# CPLD.net
KiCad netlist of a schematic drawn in Altium Designer
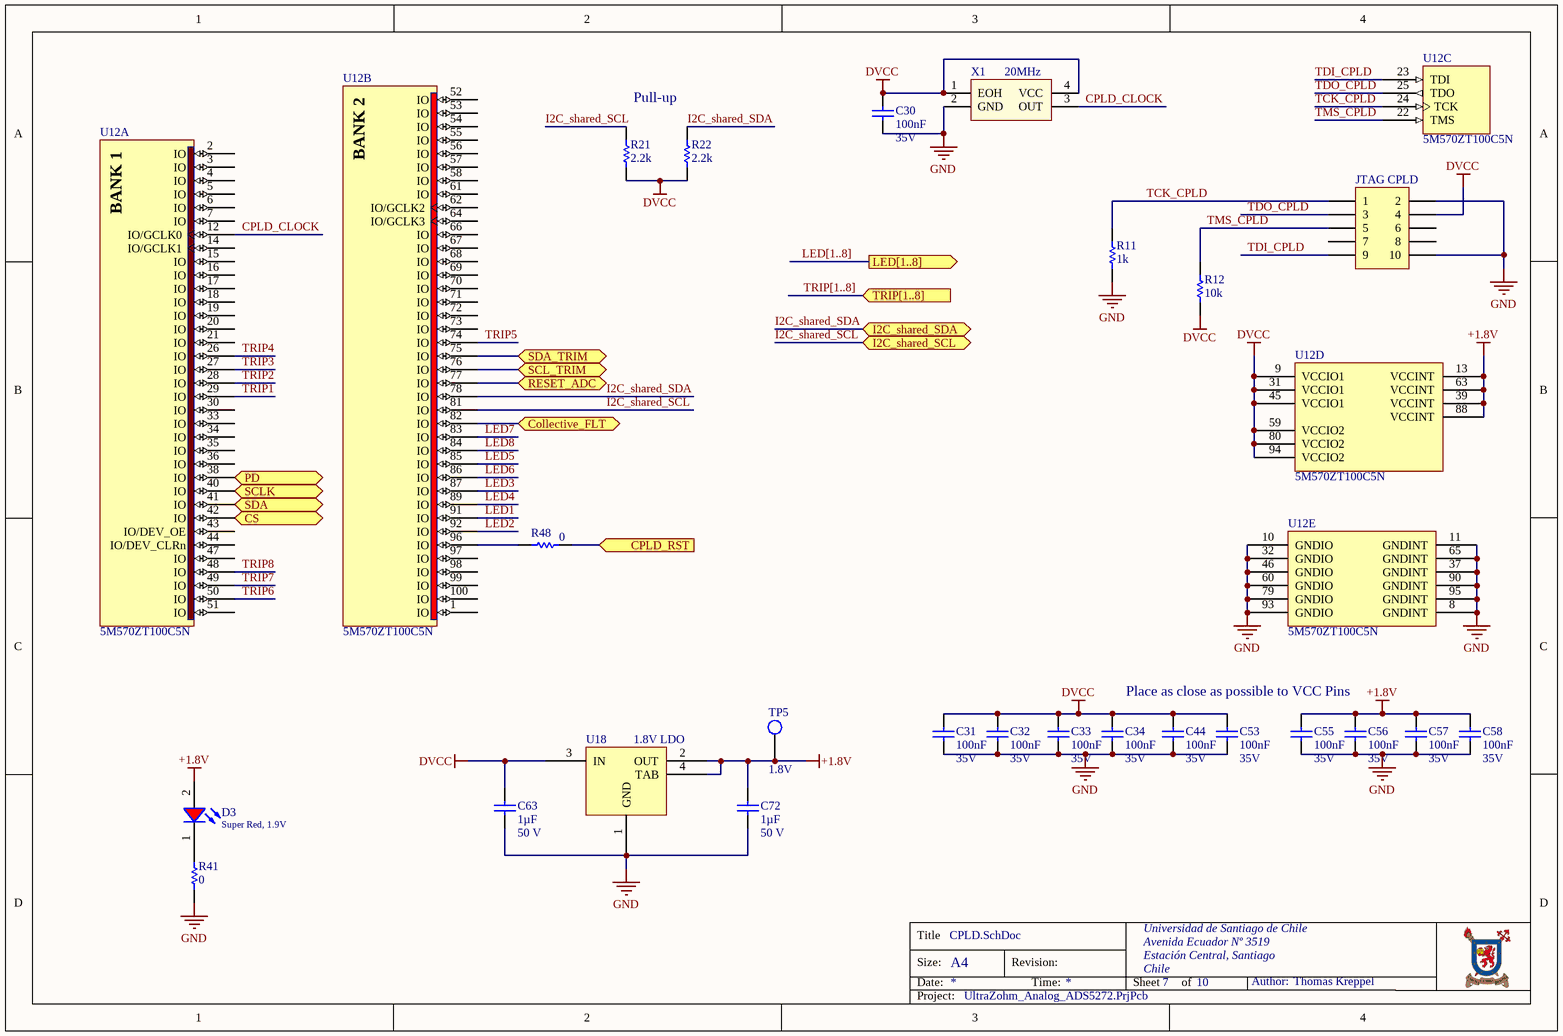
[diagram p0: CPLD.SchDoc]

(export (version "E")
  (design (tool "Eeschema 10.0.6"))
  (components
    (comp (ref "C30")
      (value "100nF")
      (footprint "CAP_0603")
      (description "Capacitor")
      (fields
        (field (name "MPN") "C0603C104M5RACTU")
        (field (name "MF") "KEMET")
        (field (name "VOLTAGE") "35V")
        (field (name "PUBLISHER") "Altium Limited")
      )
      (libsource (lib "Componentes_SOC") (part "Cap_0603"))
    )
    (comp (ref "C31")
      (value "100nF")
      (footprint "CAP_0603")
      (description "Capacitor")
      (fields
        (field (name "MPN") "C0603C104M5RACTU")
        (field (name "MF") "KEMET")
        (field (name "VOLTAGE") "35V")
        (field (name "PUBLISHER") "Altium Limited")
      )
      (libsource (lib "Componentes_SOC") (part "Cap_0603"))
    )
    (comp (ref "C32")
      (value "100nF")
      (footprint "CAP_0603")
      (description "Capacitor")
      (fields
        (field (name "MPN") "C0603C104M5RACTU")
        (field (name "MF") "KEMET")
        (field (name "VOLTAGE") "35V")
        (field (name "PUBLISHER") "Altium Limited")
      )
      (libsource (lib "Componentes_SOC") (part "Cap_0603"))
    )
    (comp (ref "C33")
      (value "100nF")
      (footprint "CAP_0603")
      (description "Capacitor")
      (fields
        (field (name "MPN") "C0603C104M5RACTU")
        (field (name "MF") "KEMET")
        (field (name "VOLTAGE") "35V")
        (field (name "PUBLISHER") "Altium Limited")
      )
      (libsource (lib "Componentes_SOC") (part "Cap_0603"))
    )
    (comp (ref "C34")
      (value "100nF")
      (footprint "CAP_0603")
      (description "Capacitor")
      (fields
        (field (name "MPN") "C0603C104M5RACTU")
        (field (name "MF") "KEMET")
        (field (name "VOLTAGE") "35V")
        (field (name "PUBLISHER") "Altium Limited")
      )
      (libsource (lib "Componentes_SOC") (part "Cap_0603"))
    )
    (comp (ref "C44")
      (value "100nF")
      (footprint "CAP_0603")
      (description "Capacitor")
      (fields
        (field (name "MPN") "C0603C104M5RACTU")
        (field (name "MF") "KEMET")
        (field (name "VOLTAGE") "35V")
        (field (name "PUBLISHER") "Altium Limited")
      )
      (libsource (lib "Componentes_SOC") (part "Cap_0603"))
    )
    (comp (ref "C53")
      (value "100nF")
      (footprint "CAP_0603")
      (description "Capacitor")
      (fields
        (field (name "MPN") "C0603C104M5RACTU")
        (field (name "MF") "KEMET")
        (field (name "VOLTAGE") "35V")
        (field (name "PUBLISHER") "Altium Limited")
      )
      (libsource (lib "Componentes_SOC") (part "Cap_0603"))
    )
    (comp (ref "C55")
      (value "100nF")
      (footprint "CAP_0603")
      (description "Capacitor")
      (fields
        (field (name "MPN") "C0603C104M5RACTU")
        (field (name "MF") "KEMET")
        (field (name "VOLTAGE") "35V")
        (field (name "PUBLISHER") "Altium Limited")
      )
      (libsource (lib "Componentes_SOC") (part "Cap_0603"))
    )
    (comp (ref "C56")
      (value "100nF")
      (footprint "CAP_0603")
      (description "Capacitor")
      (fields
        (field (name "MPN") "C0603C104M5RACTU")
        (field (name "MF") "KEMET")
        (field (name "VOLTAGE") "35V")
        (field (name "PUBLISHER") "Altium Limited")
      )
      (libsource (lib "Componentes_SOC") (part "Cap_0603"))
    )
    (comp (ref "C57")
      (value "100nF")
      (footprint "CAP_0603")
      (description "Capacitor")
      (fields
        (field (name "MPN") "C0603C104M5RACTU")
        (field (name "MF") "KEMET")
        (field (name "VOLTAGE") "35V")
        (field (name "PUBLISHER") "Altium Limited")
      )
      (libsource (lib "Componentes_SOC") (part "Cap_0603"))
    )
    (comp (ref "C58")
      (value "100nF")
      (footprint "CAP_0603")
      (description "Capacitor")
      (fields
        (field (name "MPN") "C0603C104M5RACTU")
        (field (name "MF") "KEMET")
        (field (name "VOLTAGE") "35V")
        (field (name "PUBLISHER") "Altium Limited")
      )
      (libsource (lib "Componentes_SOC") (part "Cap_0603"))
    )
    (comp (ref "C63")
      (value "1µF")
      (footprint "CAP_0603")
      (description "Capacitor Ceramic")
      (fields
        (field (name "MPN") "C0603C105K3RACTU")
        (field (name "VOLTAGE") "50 V")
        (field (name "MF") "KEMET")
      )
      (libsource (lib "Componentes_SOC") (part "Cap_0603"))
    )
    (comp (ref "C72")
      (value "1µF")
      (footprint "CAP_0603")
      (description "Capacitor Ceramic")
      (fields
        (field (name "MPN") "C0603C105K3RACTU")
        (field (name "VOLTAGE") "50 V")
        (field (name "MF") "KEMET")
      )
      (libsource (lib "Componentes_SOC") (part "Cap_0603"))
    )
    (comp (ref "D3")
      (value "Super Red, 1.9V")
      (footprint "WL-SMCW_0603_H=0.7mm")
      (description "WL-SMCW SMT Mono-color Chip LED Waterclear, size 0603, Super Red, 1.9V, 140deg")
      (fields (field (name "MPN") "150060SS75000") (field (name "MF") "Wurth Elektronik"))
      (libsource (lib "Componentes_SOC") (part "150060SS75000"))
    )
    (comp (ref "JTAG CPLD")
      (value "~")
      (footprint "Footprints_SOC:HEADER_JTAG - MAXII Horizontal")
      (description "Header, 5-Pin, Dual row, Vertical")
      (fields (field (name "PUBLISHER") "Altium Limited"))
      (libsource (lib "Componentes_SOC") (part "Header JTAG_MAXII"))
    )
    (comp (ref "R11")
      (value "1k")
      (footprint "RES_0603")
      (fields
        (field (name "MPN") "RC0603FR-071KL")
        (field (name "TOLERANCE") "1%")
        (field (name "PUBLISHER") "Altium Limited")
      )
      (libsource (lib "Componentes_SOC") (part "Res0603"))
    )
    (comp (ref "R12")
      (value "10k")
      (footprint "RES_0603")
      (fields (field (name "TOLERANCE") "1%") (field (name "PUBLISHER") "Altium Limited"))
      (libsource (lib "Componentes_SOC") (part "Res0603"))
    )
    (comp (ref "R21")
      (value "2.2k")
      (footprint "RES_0603")
      (fields
        (field (name "MPN") "RC0603FR-072K2L")
        (field (name "TOLERANCE") "1%")
        (field (name "PUBLISHER") "Altium Limited")
      )
      (libsource (lib "Componentes_SOC") (part "Res0603"))
    )
    (comp (ref "R22")
      (value "2.2k")
      (footprint "RES_0603")
      (fields
        (field (name "MPN") "RC0603FR-072K2L")
        (field (name "TOLERANCE") "1%")
        (field (name "PUBLISHER") "Altium Limited")
      )
      (libsource (lib "Componentes_SOC") (part "Res0603"))
    )
    (comp (ref "R41")
      (value "0")
      (footprint "RES_0603")
      (fields (field (name "TOLERANCE") "1%") (field (name "PUBLISHER") "Altium Limited"))
      (libsource (lib "Componentes_SOC") (part "Res0603"))
    )
    (comp (ref "R48")
      (value "0")
      (footprint "RES_0603")
      (fields (field (name "TOLERANCE") "1%") (field (name "PUBLISHER") "Altium Limited"))
      (libsource (lib "Componentes_SOC") (part "Res0603"))
    )
    (comp (ref "TP5")
      (value "1.8V")
      (footprint "TP_1.6mm")
      (description "1.6mm Test Point Keystone")
      (fields
        (field (name "MANUFACTURER") "Keystone Electronics")
        (field (name "MF") "Keystone")
        (field (name "CREATED") "2020_04_Kreppel")
      )
      (libsource (lib "Componentes_SOC") (part "TP"))
    )
    (comp (ref "U12")
      (value "5M570ZT100C5N")
      (footprint "TQFP100_N")
      (description "MAX V CPLD 440MC 9NS 100TQFP")
      (libsource (lib "Componentes_SOC") (part "5M570ZT100C5N"))
    )
    (comp (ref "U18")
      (value "1.8V LDO")
      (footprint "SOT230P700X170-4N")
      (description "1A Positive 1.8V Fixed-Voltage Low-Dropout Regulator")
      (fields (field (name "MANUFACTURER") "Texas Instruments") (field (name "CREATED") "2020_04_Kreppel"))
      (libsource (lib "Componentes_SOC") (part "TLV1117LV18DCYR"))
    )
    (comp (ref "X1")
      (value "20MHz")
      (footprint "CRYSTALOSC")
      (description "Oscilador 20MHz")
      (libsource (lib "Componentes_SOC") (part "Oscilador_1"))
    )
  )
  (nets
    (net (code "1") (name "+1.8V") (class "Default")
      (node (ref "C55") (pin "1") (pinfunction "1_1") (pintype "passive"))
      (node (ref "C56") (pin "1") (pinfunction "1_1") (pintype "passive"))
      (node (ref "C57") (pin "1") (pinfunction "1_1") (pintype "passive"))
      (node (ref "C58") (pin "1") (pinfunction "1_1") (pintype "passive"))
      (node (ref "C72") (pin "1") (pinfunction "1_1") (pintype "passive"))
      (node (ref "D3") (pin "2") (pinfunction "A_2") (pintype "passive"))
      (node (ref "TP5") (pin "1") (pinfunction "1_1") (pintype "passive"))
      (node (ref "U12") (pin "13") (pinfunction "VCCINT_13") (pintype "power_in"))
      (node (ref "U12") (pin "39") (pinfunction "VCCINT_39") (pintype "power_in"))
      (node (ref "U12") (pin "63") (pinfunction "VCCINT_63") (pintype "power_in"))
      (node (ref "U12") (pin "88") (pinfunction "VCCINT_88") (pintype "power_in"))
      (node (ref "U18") (pin "2") (pinfunction "OUT_2") (pintype "power_in"))
      (node (ref "U18") (pin "4") (pinfunction "TAB_4") (pintype "power_in"))
    )
    (net (code "2") (name "/CPLD_CLOCK") (class "Default")
      (node (ref "U12") (pin "12") (pinfunction "IO/GCLK0_12") (pintype "bidirectional"))
      (node (ref "X1") (pin "3") (pinfunction "OUT_3") (pintype "passive"))
    )
    (net (code "3") (name "/CPLD_RST") (class "Default")
      (node (ref "R48") (pin "1") (pinfunction "1_1") (pintype "passive"))
    )
    (net (code "4") (name "/CS") (class "Default")
      (node (ref "U12") (pin "42") (pinfunction "IO_42") (pintype "bidirectional"))
    )
    (net (code "5") (name "/Collective_FLT") (class "Default")
      (node (ref "U12") (pin "82") (pinfunction "IO_82") (pintype "bidirectional"))
    )
    (net (code "6") (name "/I2C_shared_SCL") (class "Default")
      (node (ref "R21") (pin "2") (pinfunction "2_2") (pintype "passive"))
      (node (ref "U12") (pin "81") (pinfunction "IO_81") (pintype "bidirectional"))
    )
    (net (code "7") (name "/I2C_shared_SDA") (class "Default")
      (node (ref "R22") (pin "2") (pinfunction "2_2") (pintype "passive"))
      (node (ref "U12") (pin "78") (pinfunction "IO_78") (pintype "bidirectional"))
    )
    (net (code "8") (name "/LED1") (class "Default")
      (node (ref "U12") (pin "91") (pinfunction "IO_91") (pintype "bidirectional"))
    )
    (net (code "9") (name "/LED2") (class "Default")
      (node (ref "U12") (pin "92") (pinfunction "IO_92") (pintype "bidirectional"))
    )
    (net (code "10") (name "/LED3") (class "Default")
      (node (ref "U12") (pin "87") (pinfunction "IO_87") (pintype "bidirectional"))
    )
    (net (code "11") (name "/LED4") (class "Default")
      (node (ref "U12") (pin "89") (pinfunction "IO_89") (pintype "bidirectional"))
    )
    (net (code "12") (name "/LED5") (class "Default")
      (node (ref "U12") (pin "85") (pinfunction "IO_85") (pintype "bidirectional"))
    )
    (net (code "13") (name "/LED6") (class "Default")
      (node (ref "U12") (pin "86") (pinfunction "IO_86") (pintype "bidirectional"))
    )
    (net (code "14") (name "/LED7") (class "Default")
      (node (ref "U12") (pin "83") (pinfunction "IO_83") (pintype "bidirectional"))
    )
    (net (code "15") (name "/LED8") (class "Default")
      (node (ref "U12") (pin "84") (pinfunction "IO_84") (pintype "bidirectional"))
    )
    (net (code "17") (name "/PD") (class "Default")
      (node (ref "U12") (pin "38") (pinfunction "IO_38") (pintype "bidirectional"))
    )
    (net (code "18") (name "/RESET_ADC") (class "Default")
      (node (ref "U12") (pin "77") (pinfunction "IO_77") (pintype "bidirectional"))
    )
    (net (code "19") (name "/SCLK") (class "Default")
      (node (ref "U12") (pin "40") (pinfunction "IO_40") (pintype "bidirectional"))
    )
    (net (code "20") (name "/SCL_TRIM") (class "Default")
      (node (ref "U12") (pin "76") (pinfunction "IO_76") (pintype "bidirectional"))
    )
    (net (code "21") (name "/SDA") (class "Default")
      (node (ref "U12") (pin "41") (pinfunction "IO_41") (pintype "bidirectional"))
    )
    (net (code "22") (name "/SDA_TRIM") (class "Default")
      (node (ref "U12") (pin "75") (pinfunction "IO_75") (pintype "bidirectional"))
    )
    (net (code "23") (name "/TCK_CPLD") (class "Default")
      (node (ref "JTAG CPLD") (pin "1") (pinfunction "1_1") (pintype "passive"))
      (node (ref "R11") (pin "2") (pinfunction "2_2") (pintype "passive"))
      (node (ref "U12") (pin "24") (pinfunction "TCK_24") (pintype "input"))
    )
    (net (code "24") (name "/TDI_CPLD") (class "Default")
      (node (ref "JTAG CPLD") (pin "9") (pinfunction "9_9") (pintype "passive"))
      (node (ref "U12") (pin "23") (pinfunction "TDI_23") (pintype "input"))
    )
    (net (code "25") (name "/TDO_CPLD") (class "Default")
      (node (ref "JTAG CPLD") (pin "3") (pinfunction "3_3") (pintype "passive"))
      (node (ref "U12") (pin "25") (pinfunction "TDO_25") (pintype "output"))
    )
    (net (code "26") (name "/TMS_CPLD") (class "Default")
      (node (ref "JTAG CPLD") (pin "5") (pinfunction "5_5") (pintype "passive"))
      (node (ref "R12") (pin "2") (pinfunction "2_2") (pintype "passive"))
      (node (ref "U12") (pin "22") (pinfunction "TMS_22") (pintype "input"))
    )
    (net (code "27") (name "/TRIP1") (class "Default")
      (node (ref "U12") (pin "29") (pinfunction "IO_29") (pintype "bidirectional"))
    )
    (net (code "28") (name "/TRIP2") (class "Default")
      (node (ref "U12") (pin "28") (pinfunction "IO_28") (pintype "bidirectional"))
    )
    (net (code "29") (name "/TRIP3") (class "Default")
      (node (ref "U12") (pin "27") (pinfunction "IO_27") (pintype "bidirectional"))
    )
    (net (code "30") (name "/TRIP4") (class "Default")
      (node (ref "U12") (pin "26") (pinfunction "IO_26") (pintype "bidirectional"))
    )
    (net (code "31") (name "/TRIP5") (class "Default")
      (node (ref "U12") (pin "74") (pinfunction "IO_74") (pintype "bidirectional"))
    )
    (net (code "32") (name "/TRIP6") (class "Default")
      (node (ref "U12") (pin "50") (pinfunction "IO_50") (pintype "bidirectional"))
    )
    (net (code "33") (name "/TRIP7") (class "Default")
      (node (ref "U12") (pin "49") (pinfunction "IO_49") (pintype "bidirectional"))
    )
    (net (code "34") (name "/TRIP8") (class "Default")
      (node (ref "U12") (pin "48") (pinfunction "IO_48") (pintype "bidirectional"))
    )
    (net (code "36") (name "DVCC") (class "Default")
      (node (ref "C30") (pin "1") (pinfunction "1_1") (pintype "passive"))
      (node (ref "C31") (pin "1") (pinfunction "1_1") (pintype "passive"))
      (node (ref "C32") (pin "1") (pinfunction "1_1") (pintype "passive"))
      (node (ref "C33") (pin "1") (pinfunction "1_1") (pintype "passive"))
      (node (ref "C34") (pin "1") (pinfunction "1_1") (pintype "passive"))
      (node (ref "C44") (pin "1") (pinfunction "1_1") (pintype "passive"))
      (node (ref "C53") (pin "1") (pinfunction "1_1") (pintype "passive"))
      (node (ref "C63") (pin "1") (pinfunction "1_1") (pintype "passive"))
      (node (ref "JTAG CPLD") (pin "4") (pinfunction "4_4") (pintype "passive"))
      (node (ref "R12") (pin "1") (pinfunction "1_1") (pintype "passive"))
      (node (ref "R21") (pin "1") (pinfunction "1_1") (pintype "passive"))
      (node (ref "R22") (pin "1") (pinfunction "1_1") (pintype "passive"))
      (node (ref "U12") (pin "31") (pinfunction "VCCIO1_31") (pintype "power_in"))
      (node (ref "U12") (pin "45") (pinfunction "VCCIO1_45") (pintype "power_in"))
      (node (ref "U12") (pin "59") (pinfunction "VCCIO2_59") (pintype "power_in"))
      (node (ref "U12") (pin "80") (pinfunction "VCCIO2_80") (pintype "power_in"))
      (node (ref "U12") (pin "9") (pinfunction "VCCIO1_9") (pintype "power_in"))
      (node (ref "U12") (pin "94") (pinfunction "VCCIO2_94") (pintype "power_in"))
      (node (ref "U18") (pin "3") (pinfunction "IN_3") (pintype "power_in"))
      (node (ref "X1") (pin "1") (pinfunction "EOH_1") (pintype "passive"))
      (node (ref "X1") (pin "4") (pinfunction "VCC_4") (pintype "passive"))
    )
    (net (code "37") (name "GND") (class "Default")
      (node (ref "C30") (pin "2") (pinfunction "2_2") (pintype "passive"))
      (node (ref "C31") (pin "2") (pinfunction "2_2") (pintype "passive"))
      (node (ref "C32") (pin "2") (pinfunction "2_2") (pintype "passive"))
      (node (ref "C33") (pin "2") (pinfunction "2_2") (pintype "passive"))
      (node (ref "C34") (pin "2") (pinfunction "2_2") (pintype "passive"))
      (node (ref "C44") (pin "2") (pinfunction "2_2") (pintype "passive"))
      (node (ref "C53") (pin "2") (pinfunction "2_2") (pintype "passive"))
      (node (ref "C55") (pin "2") (pinfunction "2_2") (pintype "passive"))
      (node (ref "C56") (pin "2") (pinfunction "2_2") (pintype "passive"))
      (node (ref "C57") (pin "2") (pinfunction "2_2") (pintype "passive"))
      (node (ref "C58") (pin "2") (pinfunction "2_2") (pintype "passive"))
      (node (ref "C63") (pin "2") (pinfunction "2_2") (pintype "passive"))
      (node (ref "C72") (pin "2") (pinfunction "2_2") (pintype "passive"))
      (node (ref "JTAG CPLD") (pin "10") (pinfunction "10_10") (pintype "passive"))
      (node (ref "JTAG CPLD") (pin "2") (pinfunction "2_2") (pintype "passive"))
      (node (ref "R11") (pin "1") (pinfunction "1_1") (pintype "passive"))
      (node (ref "R41") (pin "1") (pinfunction "1_1") (pintype "passive"))
      (node (ref "U12") (pin "10") (pinfunction "GNDIO_10") (pintype "power_in"))
      (node (ref "U12") (pin "11") (pinfunction "GNDINT_11") (pintype "power_in"))
      (node (ref "U12") (pin "32") (pinfunction "GNDIO_32") (pintype "power_in"))
      (node (ref "U12") (pin "37") (pinfunction "GNDINT_37") (pintype "power_in"))
      (node (ref "U12") (pin "46") (pinfunction "GNDIO_46") (pintype "power_in"))
      (node (ref "U12") (pin "60") (pinfunction "GNDIO_60") (pintype "power_in"))
      (node (ref "U12") (pin "65") (pinfunction "GNDINT_65") (pintype "power_in"))
      (node (ref "U12") (pin "79") (pinfunction "GNDIO_79") (pintype "power_in"))
      (node (ref "U12") (pin "8") (pinfunction "GNDINT_8") (pintype "power_in"))
      (node (ref "U12") (pin "90") (pinfunction "GNDINT_90") (pintype "power_in"))
      (node (ref "U12") (pin "93") (pinfunction "GNDIO_93") (pintype "power_in"))
      (node (ref "U12") (pin "95") (pinfunction "GNDINT_95") (pintype "power_in"))
      (node (ref "U18") (pin "1") (pinfunction "GND_1") (pintype "power_in"))
      (node (ref "X1") (pin "2") (pinfunction "GND_2") (pintype "passive"))
    )
    (net (code "38") (name "Net-(D3-K)") (class "Default")
      (node (ref "D3") (pin "1") (pinfunction "K_1") (pintype "passive"))
      (node (ref "R41") (pin "2") (pinfunction "2_2") (pintype "passive"))
    )
    (net (code "39") (name "Net-(R48-Pad2)") (class "Default")
      (node (ref "R48") (pin "2") (pinfunction "2_2") (pintype "passive"))
      (node (ref "U12") (pin "96") (pinfunction "IO_96") (pintype "bidirectional"))
    )
    (net (code "40") (name "unconnected-(JTAG CPLD-Pad6)") (class "Default")
      (node (ref "JTAG CPLD") (pin "6") (pinfunction "6_6") (pintype "passive"))
    )
    (net (code "41") (name "unconnected-(JTAG CPLD-Pad7)") (class "Default")
      (node (ref "JTAG CPLD") (pin "7") (pinfunction "7_7") (pintype "passive"))
    )
    (net (code "42") (name "unconnected-(JTAG CPLD-Pad8)") (class "Default")
      (node (ref "JTAG CPLD") (pin "8") (pinfunction "8_8") (pintype "passive"))
    )
    (net (code "43") (name "unconnected-(U12A-IO-Pad2)") (class "Default")
      (node (ref "U12") (pin "2") (pinfunction "IO_2") (pintype "bidirectional"))
    )
    (net (code "44") (name "unconnected-(U12A-IO-Pad3)") (class "Default")
      (node (ref "U12") (pin "3") (pinfunction "IO_3") (pintype "bidirectional"))
    )
    (net (code "45") (name "unconnected-(U12A-IO-Pad4)") (class "Default")
      (node (ref "U12") (pin "4") (pinfunction "IO_4") (pintype "bidirectional"))
    )
    (net (code "46") (name "unconnected-(U12A-IO-Pad5)") (class "Default")
      (node (ref "U12") (pin "5") (pinfunction "IO_5") (pintype "bidirectional"))
    )
    (net (code "47") (name "unconnected-(U12A-IO-Pad6)") (class "Default")
      (node (ref "U12") (pin "6") (pinfunction "IO_6") (pintype "bidirectional"))
    )
    (net (code "48") (name "unconnected-(U12A-IO-Pad7)") (class "Default")
      (node (ref "U12") (pin "7") (pinfunction "IO_7") (pintype "bidirectional"))
    )
    (net (code "49") (name "unconnected-(U12A-IO-Pad15)") (class "Default")
      (node (ref "U12") (pin "15") (pinfunction "IO_15") (pintype "bidirectional"))
    )
    (net (code "50") (name "unconnected-(U12A-IO-Pad16)") (class "Default")
      (node (ref "U12") (pin "16") (pinfunction "IO_16") (pintype "bidirectional"))
    )
    (net (code "51") (name "unconnected-(U12A-IO-Pad17)") (class "Default")
      (node (ref "U12") (pin "17") (pinfunction "IO_17") (pintype "bidirectional"))
    )
    (net (code "52") (name "unconnected-(U12A-IO-Pad18)") (class "Default")
      (node (ref "U12") (pin "18") (pinfunction "IO_18") (pintype "bidirectional"))
    )
    (net (code "53") (name "unconnected-(U12A-IO-Pad19)") (class "Default")
      (node (ref "U12") (pin "19") (pinfunction "IO_19") (pintype "bidirectional"))
    )
    (net (code "54") (name "unconnected-(U12A-IO-Pad20)") (class "Default")
      (node (ref "U12") (pin "20") (pinfunction "IO_20") (pintype "bidirectional"))
    )
    (net (code "55") (name "unconnected-(U12A-IO-Pad21)") (class "Default")
      (node (ref "U12") (pin "21") (pinfunction "IO_21") (pintype "bidirectional"))
    )
    (net (code "56") (name "unconnected-(U12A-IO-Pad30)") (class "Default")
      (node (ref "U12") (pin "30") (pinfunction "IO_30") (pintype "bidirectional"))
    )
    (net (code "57") (name "unconnected-(U12A-IO-Pad33)") (class "Default")
      (node (ref "U12") (pin "33") (pinfunction "IO_33") (pintype "bidirectional"))
    )
    (net (code "58") (name "unconnected-(U12A-IO-Pad34)") (class "Default")
      (node (ref "U12") (pin "34") (pinfunction "IO_34") (pintype "bidirectional"))
    )
    (net (code "59") (name "unconnected-(U12A-IO-Pad35)") (class "Default")
      (node (ref "U12") (pin "35") (pinfunction "IO_35") (pintype "bidirectional"))
    )
    (net (code "60") (name "unconnected-(U12A-IO-Pad36)") (class "Default")
      (node (ref "U12") (pin "36") (pinfunction "IO_36") (pintype "bidirectional"))
    )
    (net (code "61") (name "unconnected-(U12A-IO-Pad47)") (class "Default")
      (node (ref "U12") (pin "47") (pinfunction "IO_47") (pintype "bidirectional"))
    )
    (net (code "62") (name "unconnected-(U12A-IO-Pad51)") (class "Default")
      (node (ref "U12") (pin "51") (pinfunction "IO_51") (pintype "bidirectional"))
    )
    (net (code "63") (name "unconnected-(U12A-IO{slash}DEV_CLRn-Pad44)") (class "Default")
      (node (ref "U12") (pin "44") (pinfunction "IO/DEV_CLRn_44") (pintype "bidirectional"))
    )
    (net (code "64") (name "unconnected-(U12A-IO{slash}DEV_OE-Pad43)") (class "Default")
      (node (ref "U12") (pin "43") (pinfunction "IO/DEV_OE_43") (pintype "bidirectional"))
    )
    (net (code "65") (name "unconnected-(U12A-IO{slash}GCLK1-Pad14)") (class "Default")
      (node (ref "U12") (pin "14") (pinfunction "IO/GCLK1_14") (pintype "bidirectional"))
    )
    (net (code "66") (name "unconnected-(U12B-IO-Pad1)") (class "Default")
      (node (ref "U12") (pin "1") (pinfunction "IO_1") (pintype "bidirectional"))
    )
    (net (code "67") (name "unconnected-(U12B-IO-Pad52)") (class "Default")
      (node (ref "U12") (pin "52") (pinfunction "IO_52") (pintype "bidirectional"))
    )
    (net (code "68") (name "unconnected-(U12B-IO-Pad53)") (class "Default")
      (node (ref "U12") (pin "53") (pinfunction "IO_53") (pintype "bidirectional"))
    )
    (net (code "69") (name "unconnected-(U12B-IO-Pad54)") (class "Default")
      (node (ref "U12") (pin "54") (pinfunction "IO_54") (pintype "bidirectional"))
    )
    (net (code "70") (name "unconnected-(U12B-IO-Pad55)") (class "Default")
      (node (ref "U12") (pin "55") (pinfunction "IO_55") (pintype "bidirectional"))
    )
    (net (code "71") (name "unconnected-(U12B-IO-Pad56)") (class "Default")
      (node (ref "U12") (pin "56") (pinfunction "IO_56") (pintype "bidirectional"))
    )
    (net (code "72") (name "unconnected-(U12B-IO-Pad57)") (class "Default")
      (node (ref "U12") (pin "57") (pinfunction "IO_57") (pintype "bidirectional"))
    )
    (net (code "73") (name "unconnected-(U12B-IO-Pad58)") (class "Default")
      (node (ref "U12") (pin "58") (pinfunction "IO_58") (pintype "bidirectional"))
    )
    (net (code "74") (name "unconnected-(U12B-IO-Pad61)") (class "Default")
      (node (ref "U12") (pin "61") (pinfunction "IO_61") (pintype "bidirectional"))
    )
    (net (code "75") (name "unconnected-(U12B-IO-Pad66)") (class "Default")
      (node (ref "U12") (pin "66") (pinfunction "IO_66") (pintype "bidirectional"))
    )
    (net (code "76") (name "unconnected-(U12B-IO-Pad67)") (class "Default")
      (node (ref "U12") (pin "67") (pinfunction "IO_67") (pintype "bidirectional"))
    )
    (net (code "77") (name "unconnected-(U12B-IO-Pad68)") (class "Default")
      (node (ref "U12") (pin "68") (pinfunction "IO_68") (pintype "bidirectional"))
    )
    (net (code "78") (name "unconnected-(U12B-IO-Pad69)") (class "Default")
      (node (ref "U12") (pin "69") (pinfunction "IO_69") (pintype "bidirectional"))
    )
    (net (code "79") (name "unconnected-(U12B-IO-Pad70)") (class "Default")
      (node (ref "U12") (pin "70") (pinfunction "IO_70") (pintype "bidirectional"))
    )
    (net (code "80") (name "unconnected-(U12B-IO-Pad71)") (class "Default")
      (node (ref "U12") (pin "71") (pinfunction "IO_71") (pintype "bidirectional"))
    )
    (net (code "81") (name "unconnected-(U12B-IO-Pad72)") (class "Default")
      (node (ref "U12") (pin "72") (pinfunction "IO_72") (pintype "bidirectional"))
    )
    (net (code "82") (name "unconnected-(U12B-IO-Pad73)") (class "Default")
      (node (ref "U12") (pin "73") (pinfunction "IO_73") (pintype "bidirectional"))
    )
    (net (code "83") (name "unconnected-(U12B-IO-Pad97)") (class "Default")
      (node (ref "U12") (pin "97") (pinfunction "IO_97") (pintype "bidirectional"))
    )
    (net (code "84") (name "unconnected-(U12B-IO-Pad98)") (class "Default")
      (node (ref "U12") (pin "98") (pinfunction "IO_98") (pintype "bidirectional"))
    )
    (net (code "85") (name "unconnected-(U12B-IO-Pad99)") (class "Default")
      (node (ref "U12") (pin "99") (pinfunction "IO_99") (pintype "bidirectional"))
    )
    (net (code "86") (name "unconnected-(U12B-IO-Pad100)") (class "Default")
      (node (ref "U12") (pin "100") (pinfunction "IO_100") (pintype "bidirectional"))
    )
    (net (code "87") (name "unconnected-(U12B-IO{slash}GCLK2-Pad62)") (class "Default")
      (node (ref "U12") (pin "62") (pinfunction "IO/GCLK2_62") (pintype "bidirectional"))
    )
    (net (code "88") (name "unconnected-(U12B-IO{slash}GCLK3-Pad64)") (class "Default")
      (node (ref "U12") (pin "64") (pinfunction "IO/GCLK3_64") (pintype "bidirectional"))
    )
  )
)
